# wheather_board_definitivo_-_ESP32.net
KiCad netlist of a schematic drawn in EAGLE
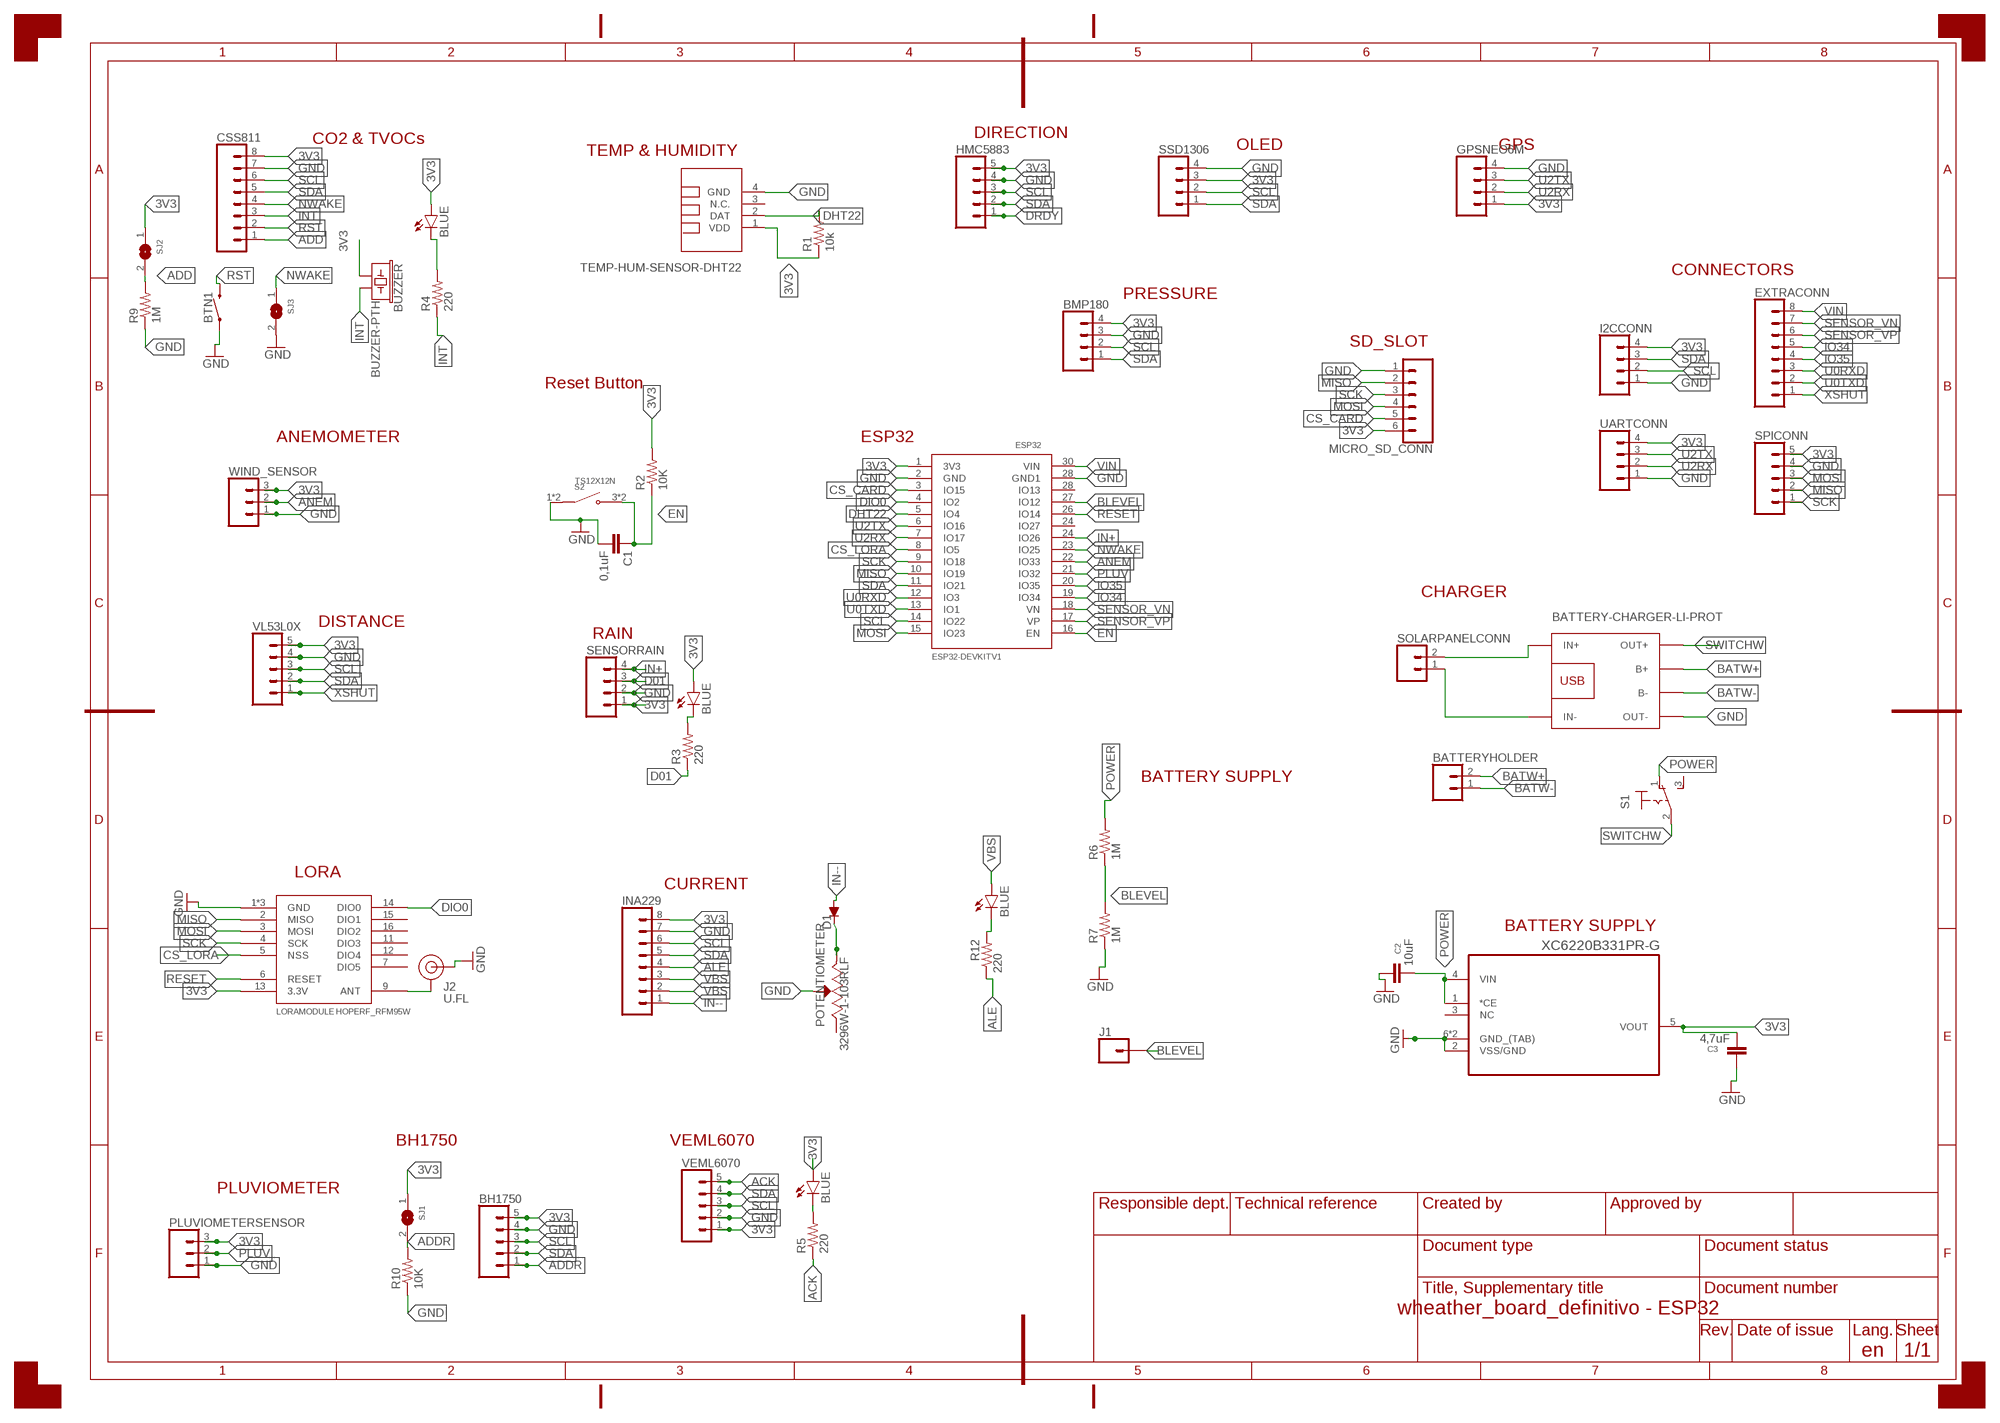
[diagram p0: schematic, sheet 1]

(export (version "E")
  (design (tool "Eeschema 10.0.6"))
  (components
    (comp (ref "BATTERYCONN")
      (value "BATTERY-CHARGER-LI-PROT")
      (footprint "eagle-import:BATTERY-CHARGER-LI-PROT")
      (libsource (lib "eagle-import") (part "BATTERY-CHARGER-LI-PROT"))
    )
    (comp (ref "BATTERYHOLDER")
      (value "CONN_02LOCK")
      (footprint "eagle-import:1X02_LOCK")
      (libsource (lib "eagle-import") (part "CONN_02LOCK"))
    )
    (comp (ref "BH1750")
      (value "CONN_05")
      (footprint "eagle-import:1X05")
      (libsource (lib "eagle-import") (part "CONN_05"))
    )
    (comp (ref "BMP180")
      (value "CONN_04")
      (footprint "eagle-import:1X04")
      (libsource (lib "eagle-import") (part "CONN_04"))
    )
    (comp (ref "BTN1")
      (value "EN")
      (footprint "eagle-import:TACTILE_SWITCH_SMD_6.0X3.5MM")
      (libsource (lib "eagle-import") (part "MOMENTARY-SWITCH-SPST-SMD-6.0X3.5MM"))
    )
    (comp (ref "BUZZER")
      (value "BUZZER-PTH")
      (footprint "eagle-import:BUZZER-12MM")
      (libsource (lib "eagle-import") (part "BUZZER-PTH"))
    )
    (comp (ref "C1")
      (value "0,1uF")
      (footprint "eagle-import:C0603")
      (libsource (lib "eagle-import") (part "C-EUC0603"))
    )
    (comp (ref "C2")
      (value "10uF")
      (footprint "eagle-import:C0603")
      (libsource (lib "eagle-import") (part "C-EUC0603"))
    )
    (comp (ref "C3")
      (value "4,7uF")
      (footprint "eagle-import:C0603")
      (libsource (lib "eagle-import") (part "C-EUC0603"))
    )
    (comp (ref "CSS811")
      (value "CONN_08\"")
      (footprint "eagle-import:1X08")
      (libsource (lib "eagle-import") (part "CONN_08{dblquote}"))
    )
    (comp (ref "D1")
      (value "DIODE_DIODE-SOD123")
      (footprint "eagle-import:DIODE_SOD123")
      (libsource (lib "eagle-import") (part "DIODE_DIODE-SOD123"))
    )
    (comp (ref "DHT22")
      (value "TEMP-HUM-SENSOR-DHT22")
      (footprint "eagle-import:TEMP-HUM-SENSOR-DHT22")
      (libsource (lib "eagle-import") (part "TEMP-HUM-SENSOR-DHT22"))
    )
    (comp (ref "ESP32")
      (value "ESP32DEVKITV1")
      (footprint "eagle-import:ESP32-DEVKITV1")
      (libsource (lib "eagle-import") (part "ESP32DEVKITV1"))
    )
    (comp (ref "EXTRACONN")
      (value "CONN_08\"")
      (footprint "eagle-import:1X08")
      (libsource (lib "eagle-import") (part "CONN_08{dblquote}"))
    )
    (comp (ref "GPSNEO6M")
      (value "CONN_04")
      (footprint "eagle-import:1X04")
      (libsource (lib "eagle-import") (part "CONN_04"))
    )
    (comp (ref "HMC5883")
      (value "CONN_05JST-VERT")
      (footprint "eagle-import:JST-5-PTH-VERT")
      (libsource (lib "eagle-import") (part "CONN_05JST-VERT"))
    )
    (comp (ref "I2CCONN")
      (value "CONN_04")
      (footprint "eagle-import:1X04")
      (libsource (lib "eagle-import") (part "CONN_04"))
    )
    (comp (ref "INA229")
      (value "CONN_08\"")
      (footprint "eagle-import:1X08")
      (libsource (lib "eagle-import") (part "CONN_08{dblquote}"))
    )
    (comp (ref "J1")
      (value "CONN_01")
      (footprint "eagle-import:1X01")
      (libsource (lib "eagle-import") (part "CONN_01"))
    )
    (comp (ref "J2")
      (value "U.FL")
      (footprint "eagle-import:U.FL")
      (libsource (lib "eagle-import") (part "U.FL2PIN"))
    )
    (comp (ref "LED1")
      (value "BLUE")
      (footprint "eagle-import:LED-0603")
      (libsource (lib "eagle-import") (part "LED-BLUE0603"))
    )
    (comp (ref "LED2")
      (value "BLUE")
      (footprint "eagle-import:LED-0603")
      (libsource (lib "eagle-import") (part "LED-BLUE0603"))
    )
    (comp (ref "LED3")
      (value "BLUE")
      (footprint "eagle-import:LED-0603")
      (libsource (lib "eagle-import") (part "LED-BLUE0603"))
    )
    (comp (ref "LED4")
      (value "BLUE")
      (footprint "eagle-import:LED-0603")
      (libsource (lib "eagle-import") (part "LED-BLUE0603"))
    )
    (comp (ref "LORAMODULE")
      (value "HOPERF_RFM95W")
      (footprint "eagle-import:HOPERF_RFM95W")
      (libsource (lib "eagle-import") (part "HOPERF_RFM95W"))
    )
    (comp (ref "MICRO_SD_CONN")
      (value "CONN_06LOCK")
      (footprint "eagle-import:1X06_LOCK")
      (libsource (lib "eagle-import") (part "CONN_06LOCK"))
    )
    (comp (ref "PLUVIOMETERSENSOR")
      (value "CONN_03JST-PTH-VERT")
      (footprint "eagle-import:JST-3-PTH-VERT")
      (libsource (lib "eagle-import") (part "CONN_03JST-PTH-VERT"))
    )
    (comp (ref "POTENTIOMETER")
      (value "3296W-1-103RLF")
      (footprint "eagle-import:TRIM_3296W-1-103RLF")
      (fields (field (name "MF") "Bourns"))
      (libsource (lib "eagle-import") (part "3296W-1-103RLF"))
    )
    (comp (ref "R1")
      (value "10k")
      (footprint "eagle-import:R0603")
      (libsource (lib "eagle-import") (part "R-US_R0603"))
    )
    (comp (ref "R2")
      (value "10K")
      (footprint "eagle-import:R0603")
      (libsource (lib "eagle-import") (part "R-US_R0603"))
    )
    (comp (ref "R3")
      (value "220")
      (footprint "eagle-import:R0603")
      (libsource (lib "eagle-import") (part "R-US_R0603"))
    )
    (comp (ref "R4")
      (value "220")
      (footprint "eagle-import:R0603")
      (libsource (lib "eagle-import") (part "R-US_R0603"))
    )
    (comp (ref "R5")
      (value "220")
      (footprint "eagle-import:R0603")
      (libsource (lib "eagle-import") (part "R-US_R0603"))
    )
    (comp (ref "R6")
      (value "1M")
      (footprint "eagle-import:R0603")
      (libsource (lib "eagle-import") (part "R-US_R0603"))
    )
    (comp (ref "R7")
      (value "1M")
      (footprint "eagle-import:R0603")
      (libsource (lib "eagle-import") (part "R-US_R0603"))
    )
    (comp (ref "R9")
      (value "1M")
      (footprint "eagle-import:R0603")
      (libsource (lib "eagle-import") (part "R-US_R0603"))
    )
    (comp (ref "R10")
      (value "10K")
      (footprint "eagle-import:R0603")
      (libsource (lib "eagle-import") (part "R-US_R0603"))
    )
    (comp (ref "R12")
      (value "220")
      (footprint "eagle-import:R0603")
      (libsource (lib "eagle-import") (part "R-US_R0603"))
    )
    (comp (ref "S1")
      (value "320-916")
      (footprint "eagle-import:320-916")
      (libsource (lib "eagle-import") (part "320-916"))
    )
    (comp (ref "S2")
      (value "TS12X12N")
      (footprint "eagle-import:SW_TS12X12N")
      (fields (field (name "MF") "Aitendo"))
      (libsource (lib "eagle-import") (part "TS12X12N"))
    )
    (comp (ref "SENSORRAIN")
      (value "CONN_04")
      (footprint "eagle-import:1X04")
      (libsource (lib "eagle-import") (part "CONN_04"))
    )
    (comp (ref "SJ1")
      (value "SOLDERJUMPER")
      (footprint "eagle-import:SOLDERJUMPER_ARROW_NOPASTE")
      (libsource (lib "eagle-import") (part "SOLDERJUMPER"))
    )
    (comp (ref "SJ2")
      (value "SOLDERJUMPER")
      (footprint "eagle-import:SOLDERJUMPER_ARROW_NOPASTE")
      (libsource (lib "eagle-import") (part "SOLDERJUMPER"))
    )
    (comp (ref "SJ3")
      (value "SOLDERJUMPER")
      (footprint "eagle-import:SOLDERJUMPER_ARROW_NOPASTE")
      (libsource (lib "eagle-import") (part "SOLDERJUMPER"))
    )
    (comp (ref "SOLARPANELCONN")
      (value "CONN_02LOCK")
      (footprint "eagle-import:1X02_LOCK")
      (libsource (lib "eagle-import") (part "CONN_02LOCK"))
    )
    (comp (ref "SPICONN")
      (value "CONN_05")
      (footprint "eagle-import:1X05")
      (libsource (lib "eagle-import") (part "CONN_05"))
    )
    (comp (ref "SSD1306")
      (value "CONN_04")
      (footprint "eagle-import:1X04")
      (libsource (lib "eagle-import") (part "CONN_04"))
    )
    (comp (ref "UARTCONN")
      (value "CONN_04")
      (footprint "eagle-import:1X04")
      (libsource (lib "eagle-import") (part "CONN_04"))
    )
    (comp (ref "VEML6070")
      (value "CONN_05")
      (footprint "eagle-import:1X05")
      (libsource (lib "eagle-import") (part "CONN_05"))
    )
    (comp (ref "VL53L0X")
      (value "CONN_05JST-VERT")
      (footprint "eagle-import:JST-5-PTH-VERT")
      (libsource (lib "eagle-import") (part "CONN_05JST-VERT"))
    )
    (comp (ref "WIND_SENSOR")
      (value "CONN_03JST-PTH-VERT")
      (footprint "eagle-import:JST-3-PTH-VERT")
      (libsource (lib "eagle-import") (part "CONN_03JST-PTH-VERT"))
    )
    (comp (ref "XC6220B331PR-G")
      (value "XC6210B332PR")
      (footprint "eagle-import:XC6210B332PR")
      (fields (field (name "MF") "Microchip") (field (name "MP") "MCP1826T-3002E/DC"))
      (libsource (lib "eagle-import") (part "XC6210B332PR"))
    )
  )
  (nets
    (net (code "1") (name "3V3") (class "Default")
      (node (ref "BH1750") (pin "5") (pinfunction "5_5") (pintype "passive"))
      (node (ref "BMP180") (pin "4") (pinfunction "4_4") (pintype "passive"))
      (node (ref "BUZZER") (pin "+") (pinfunction "1_+") (pintype "passive"))
      (node (ref "C3") (pin "2") (pinfunction "2_2") (pintype "passive"))
      (node (ref "CSS811") (pin "8") (pinfunction "8_8") (pintype "passive"))
      (node (ref "DHT22") (pin "1") (pinfunction "VDD_1") (pintype "power_in"))
      (node (ref "ESP32") (pin "1") (pinfunction "3V3_1") (pintype "bidirectional"))
      (node (ref "GPSNEO6M") (pin "1") (pinfunction "1_1") (pintype "passive"))
      (node (ref "HMC5883") (pin "5") (pinfunction "5_5") (pintype "passive"))
      (node (ref "I2CCONN") (pin "4") (pinfunction "4_4") (pintype "passive"))
      (node (ref "INA229") (pin "8") (pinfunction "8_8") (pintype "passive"))
      (node (ref "LED1") (pin "A") (pinfunction "A_A") (pintype "passive"))
      (node (ref "LED2") (pin "A") (pinfunction "A_A") (pintype "passive"))
      (node (ref "LED3") (pin "A") (pinfunction "A_A") (pintype "passive"))
      (node (ref "LORAMODULE") (pin "13") (pinfunction "3.3V_13") (pintype "power_in"))
      (node (ref "MICRO_SD_CONN") (pin "6") (pinfunction "6_6") (pintype "passive"))
      (node (ref "PLUVIOMETERSENSOR") (pin "3") (pinfunction "3_3") (pintype "passive"))
      (node (ref "R1") (pin "1") (pinfunction "1_1") (pintype "passive"))
      (node (ref "R2") (pin "2") (pinfunction "2_2") (pintype "passive"))
      (node (ref "SENSORRAIN") (pin "1") (pinfunction "1_1") (pintype "passive"))
      (node (ref "SJ1") (pin "1") (pinfunction "1_1") (pintype "passive"))
      (node (ref "SJ2") (pin "1") (pinfunction "1_1") (pintype "passive"))
      (node (ref "SPICONN") (pin "5") (pinfunction "5_5") (pintype "passive"))
      (node (ref "SSD1306") (pin "3") (pinfunction "3_3") (pintype "passive"))
      (node (ref "UARTCONN") (pin "4") (pinfunction "4_4") (pintype "passive"))
      (node (ref "VEML6070") (pin "1") (pinfunction "1_1") (pintype "passive"))
      (node (ref "VL53L0X") (pin "5") (pinfunction "5_5") (pintype "passive"))
      (node (ref "WIND_SENSOR") (pin "3") (pinfunction "3_3") (pintype "passive"))
      (node (ref "XC6220B331PR-G") (pin "5") (pinfunction "VOUT_5") (pintype "output"))
    )
    (net (code "2") (name "ACK") (class "Default")
      (node (ref "R5") (pin "1") (pinfunction "1_1") (pintype "passive"))
      (node (ref "VEML6070") (pin "5") (pinfunction "5_5") (pintype "passive"))
    )
    (net (code "3") (name "ADD") (class "Default")
      (node (ref "CSS811") (pin "1") (pinfunction "1_1") (pintype "passive"))
      (node (ref "R9") (pin "2") (pinfunction "2_2") (pintype "passive"))
      (node (ref "SJ2") (pin "2") (pinfunction "2_2") (pintype "passive"))
    )
    (net (code "4") (name "ADDR") (class "Default")
      (node (ref "BH1750") (pin "1") (pinfunction "1_1") (pintype "passive"))
      (node (ref "R10") (pin "2") (pinfunction "2_2") (pintype "passive"))
      (node (ref "SJ1") (pin "2") (pinfunction "2_2") (pintype "passive"))
    )
    (net (code "5") (name "ALE") (class "Default")
      (node (ref "INA229") (pin "4") (pinfunction "4_4") (pintype "passive"))
      (node (ref "R12") (pin "1") (pinfunction "1_1") (pintype "passive"))
    )
    (net (code "6") (name "ANEM") (class "Default")
      (node (ref "ESP32") (pin "22") (pinfunction "IO33_22") (pintype "bidirectional"))
      (node (ref "WIND_SENSOR") (pin "2") (pinfunction "2_2") (pintype "passive"))
    )
    (net (code "7") (name "BATW+") (class "Default")
      (node (ref "BATTERYCONN") (pin "B+") (pinfunction "B+_B+") (pintype "bidirectional"))
      (node (ref "BATTERYHOLDER") (pin "2") (pinfunction "2_2") (pintype "passive"))
    )
    (net (code "8") (name "BATW-") (class "Default")
      (node (ref "BATTERYCONN") (pin "B-") (pinfunction "B-_B-") (pintype "bidirectional"))
      (node (ref "BATTERYHOLDER") (pin "1") (pinfunction "1_1") (pintype "passive"))
    )
    (net (code "9") (name "BLEVEL") (class "Default")
      (node (ref "ESP32") (pin "27") (pinfunction "IO12_27") (pintype "bidirectional"))
      (node (ref "J1") (pin "1") (pinfunction "1_1") (pintype "passive"))
      (node (ref "R6") (pin "1") (pinfunction "1_1") (pintype "passive"))
      (node (ref "R7") (pin "2") (pinfunction "2_2") (pintype "passive"))
    )
    (net (code "10") (name "CS_CARD") (class "Default")
      (node (ref "ESP32") (pin "3") (pinfunction "IO15_3") (pintype "bidirectional"))
      (node (ref "MICRO_SD_CONN") (pin "5") (pinfunction "5_5") (pintype "passive"))
    )
    (net (code "11") (name "CS_LORA") (class "Default")
      (node (ref "ESP32") (pin "8") (pinfunction "IO5_8") (pintype "bidirectional"))
      (node (ref "LORAMODULE") (pin "5") (pinfunction "NSS_5") (pintype "input"))
    )
    (net (code "12") (name "D01") (class "Default")
      (node (ref "R3") (pin "1") (pinfunction "1_1") (pintype "passive"))
      (node (ref "SENSORRAIN") (pin "3") (pinfunction "3_3") (pintype "passive"))
    )
    (net (code "13") (name "DHT22") (class "Default")
      (node (ref "DHT22") (pin "2") (pinfunction "DAT_2") (pintype "bidirectional"))
      (node (ref "ESP32") (pin "5") (pinfunction "IO4_5") (pintype "bidirectional"))
      (node (ref "R1") (pin "2") (pinfunction "2_2") (pintype "passive"))
    )
    (net (code "14") (name "DIO0") (class "Default")
      (node (ref "ESP32") (pin "4") (pinfunction "IO2_4") (pintype "bidirectional"))
      (node (ref "LORAMODULE") (pin "14") (pinfunction "DIO0_14") (pintype "bidirectional"))
    )
    (net (code "15") (name "DRDY") (class "Default")
      (node (ref "HMC5883") (pin "1") (pinfunction "1_1") (pintype "passive"))
    )
    (net (code "16") (name "EN") (class "Default")
      (node (ref "C1") (pin "1") (pinfunction "1_1") (pintype "passive"))
      (node (ref "ESP32") (pin "16") (pinfunction "EN_16") (pintype "bidirectional"))
      (node (ref "R2") (pin "1") (pinfunction "1_1") (pintype "passive"))
      (node (ref "S2") (pin "3") (pinfunction "3_4_3") (pintype "passive"))
      (node (ref "S2") (pin "4") (pinfunction "3_4_4") (pintype "passive"))
    )
    (net (code "17") (name "GND") (class "Default")
      (node (ref "BATTERYCONN") (pin "OUT-") (pinfunction "OUT-_OUT-") (pintype "bidirectional"))
      (node (ref "BH1750") (pin "4") (pinfunction "4_4") (pintype "passive"))
      (node (ref "BMP180") (pin "3") (pinfunction "3_3") (pintype "passive"))
      (node (ref "BTN1") (pin "1") (pinfunction "1_1") (pintype "passive"))
      (node (ref "C1") (pin "2") (pinfunction "2_2") (pintype "passive"))
      (node (ref "C2") (pin "1") (pinfunction "1_1") (pintype "passive"))
      (node (ref "C3") (pin "1") (pinfunction "1_1") (pintype "passive"))
      (node (ref "CSS811") (pin "7") (pinfunction "7_7") (pintype "passive"))
      (node (ref "DHT22") (pin "4") (pinfunction "GND_4") (pintype "power_in"))
      (node (ref "ESP32") (pin "2") (pinfunction "GND_2") (pintype "bidirectional"))
      (node (ref "ESP32") (pin "28") (pinfunction "GND1_28") (pintype "bidirectional"))
      (node (ref "GPSNEO6M") (pin "4") (pinfunction "4_4") (pintype "passive"))
      (node (ref "HMC5883") (pin "4") (pinfunction "4_4") (pintype "passive"))
      (node (ref "I2CCONN") (pin "1") (pinfunction "1_1") (pintype "passive"))
      (node (ref "INA229") (pin "7") (pinfunction "7_7") (pintype "passive"))
      (node (ref "J2") (pin "FEED") (pinfunction "SIGNAL_FEED") (pintype "bidirectional"))
      (node (ref "LORAMODULE") (pin "1") (pinfunction "GND_1") (pintype "power_in"))
      (node (ref "LORAMODULE") (pin "10") (pinfunction "GND_10") (pintype "power_in"))
      (node (ref "LORAMODULE") (pin "8") (pinfunction "GND_8") (pintype "power_in"))
      (node (ref "MICRO_SD_CONN") (pin "1") (pinfunction "1_1") (pintype "passive"))
      (node (ref "PLUVIOMETERSENSOR") (pin "1") (pinfunction "1_1") (pintype "passive"))
      (node (ref "POTENTIOMETER") (pin "2") (pinfunction "WIPER_2") (pintype "passive"))
      (node (ref "R10") (pin "1") (pinfunction "1_1") (pintype "passive"))
      (node (ref "R7") (pin "1") (pinfunction "1_1") (pintype "passive"))
      (node (ref "R9") (pin "1") (pinfunction "1_1") (pintype "passive"))
      (node (ref "S2") (pin "1") (pinfunction "1_2_1") (pintype "passive"))
      (node (ref "S2") (pin "2") (pinfunction "1_2_2") (pintype "passive"))
      (node (ref "SENSORRAIN") (pin "2") (pinfunction "2_2") (pintype "passive"))
      (node (ref "SJ3") (pin "2") (pinfunction "2_2") (pintype "passive"))
      (node (ref "SPICONN") (pin "4") (pinfunction "4_4") (pintype "passive"))
      (node (ref "SSD1306") (pin "4") (pinfunction "4_4") (pintype "passive"))
      (node (ref "UARTCONN") (pin "1") (pinfunction "1_1") (pintype "passive"))
      (node (ref "VEML6070") (pin "2") (pinfunction "2_2") (pintype "passive"))
      (node (ref "VL53L0X") (pin "4") (pinfunction "4_4") (pintype "passive"))
      (node (ref "WIND_SENSOR") (pin "1") (pinfunction "1_1") (pintype "passive"))
      (node (ref "XC6220B331PR-G") (pin "2") (pinfunction "VSS/GND_2") (pintype "passive"))
      (node (ref "XC6220B331PR-G") (pin "6") (pinfunction "GND_(TAB)_6") (pintype "passive"))
      (node (ref "XC6220B331PR-G") (pin "TAB") (pinfunction "GND_(TAB)_TAB") (pintype "passive"))
    )
    (net (code "18") (name "IN+") (class "Default")
      (node (ref "ESP32") (pin "24") (pinfunction "IO26_24") (pintype "bidirectional"))
      (node (ref "SENSORRAIN") (pin "4") (pinfunction "4_4") (pintype "passive"))
    )
    (net (code "19") (name "IN--") (class "Default")
      (node (ref "D1") (pin "A") (pinfunction "A_A") (pintype "passive"))
      (node (ref "INA229") (pin "1") (pinfunction "1_1") (pintype "passive"))
    )
    (net (code "20") (name "INT") (class "Default")
      (node (ref "BUZZER") (pin "-") (pinfunction "2_-") (pintype "passive"))
      (node (ref "CSS811") (pin "3") (pinfunction "3_3") (pintype "passive"))
      (node (ref "R4") (pin "1") (pinfunction "1_1") (pintype "passive"))
    )
    (net (code "21") (name "IO34") (class "Default")
      (node (ref "ESP32") (pin "19") (pinfunction "IO34_19") (pintype "bidirectional"))
      (node (ref "EXTRACONN") (pin "5") (pinfunction "5_5") (pintype "passive"))
    )
    (net (code "22") (name "IO35") (class "Default")
      (node (ref "ESP32") (pin "20") (pinfunction "IO35_20") (pintype "bidirectional"))
      (node (ref "EXTRACONN") (pin "4") (pinfunction "4_4") (pintype "passive"))
    )
    (net (code "23") (name "MISO") (class "Default")
      (node (ref "ESP32") (pin "10") (pinfunction "IO19_10") (pintype "bidirectional"))
      (node (ref "LORAMODULE") (pin "2") (pinfunction "MISO_2") (pintype "input"))
      (node (ref "MICRO_SD_CONN") (pin "2") (pinfunction "2_2") (pintype "passive"))
      (node (ref "SPICONN") (pin "2") (pinfunction "2_2") (pintype "passive"))
    )
    (net (code "24") (name "MOSI") (class "Default")
      (node (ref "ESP32") (pin "15") (pinfunction "IO23_15") (pintype "bidirectional"))
      (node (ref "LORAMODULE") (pin "3") (pinfunction "MOSI_3") (pintype "output"))
      (node (ref "MICRO_SD_CONN") (pin "4") (pinfunction "4_4") (pintype "passive"))
      (node (ref "SPICONN") (pin "3") (pinfunction "3_3") (pintype "passive"))
    )
    (net (code "25") (name "NWAKE") (class "Default")
      (node (ref "CSS811") (pin "4") (pinfunction "4_4") (pintype "passive"))
      (node (ref "ESP32") (pin "23") (pinfunction "IO25_23") (pintype "bidirectional"))
      (node (ref "SJ3") (pin "1") (pinfunction "1_1") (pintype "passive"))
    )
    (net (code "26") (name "Net-(BATTERYCONN-PadIN+)") (class "Default")
      (node (ref "BATTERYCONN") (pin "IN+") (pinfunction "IN+_IN+") (pintype "bidirectional"))
      (node (ref "SOLARPANELCONN") (pin "2") (pinfunction "2_2") (pintype "passive"))
    )
    (net (code "27") (name "Net-(BATTERYCONN-PadIN-)") (class "Default")
      (node (ref "BATTERYCONN") (pin "IN-") (pinfunction "IN-_IN-") (pintype "bidirectional"))
      (node (ref "SOLARPANELCONN") (pin "1") (pinfunction "1_1") (pintype "passive"))
    )
    (net (code "28") (name "Net-(LED1-PadC)") (class "Default")
      (node (ref "LED1") (pin "C") (pinfunction "C_C") (pintype "passive"))
      (node (ref "R3") (pin "2") (pinfunction "2_2") (pintype "passive"))
    )
    (net (code "29") (name "Net-(LED2-PadC)") (class "Default")
      (node (ref "LED2") (pin "C") (pinfunction "C_C") (pintype "passive"))
      (node (ref "R4") (pin "2") (pinfunction "2_2") (pintype "passive"))
    )
    (net (code "30") (name "Net-(LED3-PadC)") (class "Default")
      (node (ref "LED3") (pin "C") (pinfunction "C_C") (pintype "passive"))
      (node (ref "R5") (pin "2") (pinfunction "2_2") (pintype "passive"))
    )
    (net (code "31") (name "Net-(LED4-PadC)") (class "Default")
      (node (ref "LED4") (pin "C") (pinfunction "C_C") (pintype "passive"))
      (node (ref "R12") (pin "2") (pinfunction "2_2") (pintype "passive"))
    )
    (net (code "32") (name "Net-(LORAMODULE-ANT)") (class "Default")
      (node (ref "J2") (pin "1") (pinfunction "GND_1") (pintype "bidirectional"))
      (node (ref "J2") (pin "2") (pinfunction "GND_2") (pintype "bidirectional"))
      (node (ref "LORAMODULE") (pin "9") (pinfunction "ANT_9") (pintype "bidirectional"))
    )
    (net (code "33") (name "Net-(POTENTIOMETER-CW)") (class "Default")
      (node (ref "D1") (pin "C") (pinfunction "C_C") (pintype "passive"))
      (node (ref "POTENTIOMETER") (pin "3") (pinfunction "CW_3") (pintype "passive"))
    )
    (net (code "34") (name "PLUV") (class "Default")
      (node (ref "ESP32") (pin "21") (pinfunction "IO32_21") (pintype "bidirectional"))
      (node (ref "PLUVIOMETERSENSOR") (pin "2") (pinfunction "2_2") (pintype "passive"))
    )
    (net (code "35") (name "POWER") (class "Default")
      (node (ref "C2") (pin "2") (pinfunction "2_2") (pintype "passive"))
      (node (ref "R6") (pin "2") (pinfunction "2_2") (pintype "passive"))
      (node (ref "S1") (pin "1") (pinfunction "O_1") (pintype "passive"))
      (node (ref "XC6220B331PR-G") (pin "1") (pinfunction "*CE_1") (pintype "input"))
      (node (ref "XC6220B331PR-G") (pin "4") (pinfunction "VIN_4") (pintype "input"))
    )
    (net (code "36") (name "RESET") (class "Default")
      (node (ref "ESP32") (pin "26") (pinfunction "IO14_26") (pintype "bidirectional"))
      (node (ref "LORAMODULE") (pin "6") (pinfunction "RESET_6") (pintype "bidirectional"))
    )
    (net (code "37") (name "RST") (class "Default")
      (node (ref "BTN1") (pin "2") (pinfunction "2_2") (pintype "passive"))
      (node (ref "CSS811") (pin "2") (pinfunction "2_2") (pintype "passive"))
    )
    (net (code "38") (name "SCK") (class "Default")
      (node (ref "ESP32") (pin "9") (pinfunction "IO18_9") (pintype "bidirectional"))
      (node (ref "LORAMODULE") (pin "4") (pinfunction "SCK_4") (pintype "input"))
      (node (ref "MICRO_SD_CONN") (pin "3") (pinfunction "3_3") (pintype "passive"))
      (node (ref "SPICONN") (pin "1") (pinfunction "1_1") (pintype "passive"))
    )
    (net (code "39") (name "SCL") (class "Default")
      (node (ref "BH1750") (pin "3") (pinfunction "3_3") (pintype "passive"))
      (node (ref "BMP180") (pin "2") (pinfunction "2_2") (pintype "passive"))
      (node (ref "CSS811") (pin "6") (pinfunction "6_6") (pintype "passive"))
      (node (ref "ESP32") (pin "14") (pinfunction "IO22_14") (pintype "bidirectional"))
      (node (ref "HMC5883") (pin "3") (pinfunction "3_3") (pintype "passive"))
      (node (ref "I2CCONN") (pin "2") (pinfunction "2_2") (pintype "passive"))
      (node (ref "INA229") (pin "6") (pinfunction "6_6") (pintype "passive"))
      (node (ref "SSD1306") (pin "2") (pinfunction "2_2") (pintype "passive"))
      (node (ref "VEML6070") (pin "3") (pinfunction "3_3") (pintype "passive"))
      (node (ref "VL53L0X") (pin "3") (pinfunction "3_3") (pintype "passive"))
    )
    (net (code "40") (name "SDA") (class "Default")
      (node (ref "BH1750") (pin "2") (pinfunction "2_2") (pintype "passive"))
      (node (ref "BMP180") (pin "1") (pinfunction "1_1") (pintype "passive"))
      (node (ref "CSS811") (pin "5") (pinfunction "5_5") (pintype "passive"))
      (node (ref "ESP32") (pin "11") (pinfunction "IO21_11") (pintype "bidirectional"))
      (node (ref "HMC5883") (pin "2") (pinfunction "2_2") (pintype "passive"))
      (node (ref "I2CCONN") (pin "3") (pinfunction "3_3") (pintype "passive"))
      (node (ref "INA229") (pin "5") (pinfunction "5_5") (pintype "passive"))
      (node (ref "SSD1306") (pin "1") (pinfunction "1_1") (pintype "passive"))
      (node (ref "VEML6070") (pin "4") (pinfunction "4_4") (pintype "passive"))
      (node (ref "VL53L0X") (pin "2") (pinfunction "2_2") (pintype "passive"))
    )
    (net (code "41") (name "SENSOR_VN") (class "Default")
      (node (ref "ESP32") (pin "18") (pinfunction "VN_18") (pintype "bidirectional"))
      (node (ref "EXTRACONN") (pin "7") (pinfunction "7_7") (pintype "passive"))
    )
    (net (code "42") (name "SENSOR_VP") (class "Default")
      (node (ref "ESP32") (pin "17") (pinfunction "VP_17") (pintype "bidirectional"))
      (node (ref "EXTRACONN") (pin "6") (pinfunction "6_6") (pintype "passive"))
    )
    (net (code "43") (name "SWITCHW") (class "Default")
      (node (ref "BATTERYCONN") (pin "OUT+") (pinfunction "OUT+_OUT+") (pintype "bidirectional"))
      (node (ref "S1") (pin "2") (pinfunction "P_2") (pintype "passive"))
    )
    (net (code "44") (name "U0RXD") (class "Default")
      (node (ref "ESP32") (pin "12") (pinfunction "IO3_12") (pintype "bidirectional"))
      (node (ref "EXTRACONN") (pin "3") (pinfunction "3_3") (pintype "passive"))
    )
    (net (code "45") (name "U0TXD") (class "Default")
      (node (ref "ESP32") (pin "13") (pinfunction "IO1_13") (pintype "bidirectional"))
      (node (ref "EXTRACONN") (pin "2") (pinfunction "2_2") (pintype "passive"))
    )
    (net (code "46") (name "U2RX") (class "Default")
      (node (ref "ESP32") (pin "7") (pinfunction "IO17_7") (pintype "bidirectional"))
      (node (ref "GPSNEO6M") (pin "2") (pinfunction "2_2") (pintype "passive"))
      (node (ref "UARTCONN") (pin "2") (pinfunction "2_2") (pintype "passive"))
    )
    (net (code "47") (name "U2TX") (class "Default")
      (node (ref "ESP32") (pin "6") (pinfunction "IO16_6") (pintype "bidirectional"))
      (node (ref "GPSNEO6M") (pin "3") (pinfunction "3_3") (pintype "passive"))
      (node (ref "UARTCONN") (pin "3") (pinfunction "3_3") (pintype "passive"))
    )
    (net (code "48") (name "VBS") (class "Default")
      (node (ref "INA229") (pin "2") (pinfunction "2_2") (pintype "passive"))
      (node (ref "INA229") (pin "3") (pinfunction "3_3") (pintype "passive"))
      (node (ref "LED4") (pin "A") (pinfunction "A_A") (pintype "passive"))
    )
    (net (code "49") (name "VIN") (class "Default")
      (node (ref "ESP32") (pin "30") (pinfunction "VIN_30") (pintype "bidirectional"))
      (node (ref "EXTRACONN") (pin "8") (pinfunction "8_8") (pintype "passive"))
    )
    (net (code "50") (name "XSHUT") (class "Default")
      (node (ref "EXTRACONN") (pin "1") (pinfunction "1_1") (pintype "passive"))
      (node (ref "VL53L0X") (pin "1") (pinfunction "1_1") (pintype "passive"))
    )
    (net (code "51") (name "unconnected-(DHT22-N.C.-Pad3)") (class "Default")
      (node (ref "DHT22") (pin "3") (pinfunction "N.C._3") (pintype "passive"))
    )
    (net (code "52") (name "unconnected-(ESP32-IO13-Pad28)") (class "Default")
      (node (ref "ESP32") (pin "28") (pinfunction "IO13_28") (pintype "bidirectional"))
    )
    (net (code "53") (name "unconnected-(ESP32-IO27-Pad24)") (class "Default")
      (node (ref "ESP32") (pin "24") (pinfunction "IO27_24") (pintype "bidirectional"))
    )
    (net (code "54") (name "unconnected-(LORAMODULE-DIO1-Pad15)") (class "Default")
      (node (ref "LORAMODULE") (pin "15") (pinfunction "DIO1_15") (pintype "bidirectional"))
    )
    (net (code "55") (name "unconnected-(LORAMODULE-DIO2-Pad16)") (class "Default")
      (node (ref "LORAMODULE") (pin "16") (pinfunction "DIO2_16") (pintype "bidirectional"))
    )
    (net (code "56") (name "unconnected-(LORAMODULE-DIO3-Pad11)") (class "Default")
      (node (ref "LORAMODULE") (pin "11") (pinfunction "DIO3_11") (pintype "bidirectional"))
    )
    (net (code "57") (name "unconnected-(LORAMODULE-DIO4-Pad12)") (class "Default")
      (node (ref "LORAMODULE") (pin "12") (pinfunction "DIO4_12") (pintype "bidirectional"))
    )
    (net (code "58") (name "unconnected-(LORAMODULE-DIO5-Pad7)") (class "Default")
      (node (ref "LORAMODULE") (pin "7") (pinfunction "DIO5_7") (pintype "bidirectional"))
    )
    (net (code "59") (name "unconnected-(POTENTIOMETER-CCW-Pad1)") (class "Default")
      (node (ref "POTENTIOMETER") (pin "1") (pinfunction "CCW_1") (pintype "passive"))
    )
    (net (code "60") (name "unconnected-(S1-S-Pad3)") (class "Default")
      (node (ref "S1") (pin "3") (pinfunction "S_3") (pintype "passive"))
    )
    (net (code "61") (name "unconnected-(XC6220B331PR-G-NC-Pad3)") (class "Default")
      (node (ref "XC6220B331PR-G") (pin "3") (pinfunction "NC_3") (pintype "input"))
    )
  )
)
